# NEW_LINE_1.net
KiCad netlist of a schematic drawn in EAGLE
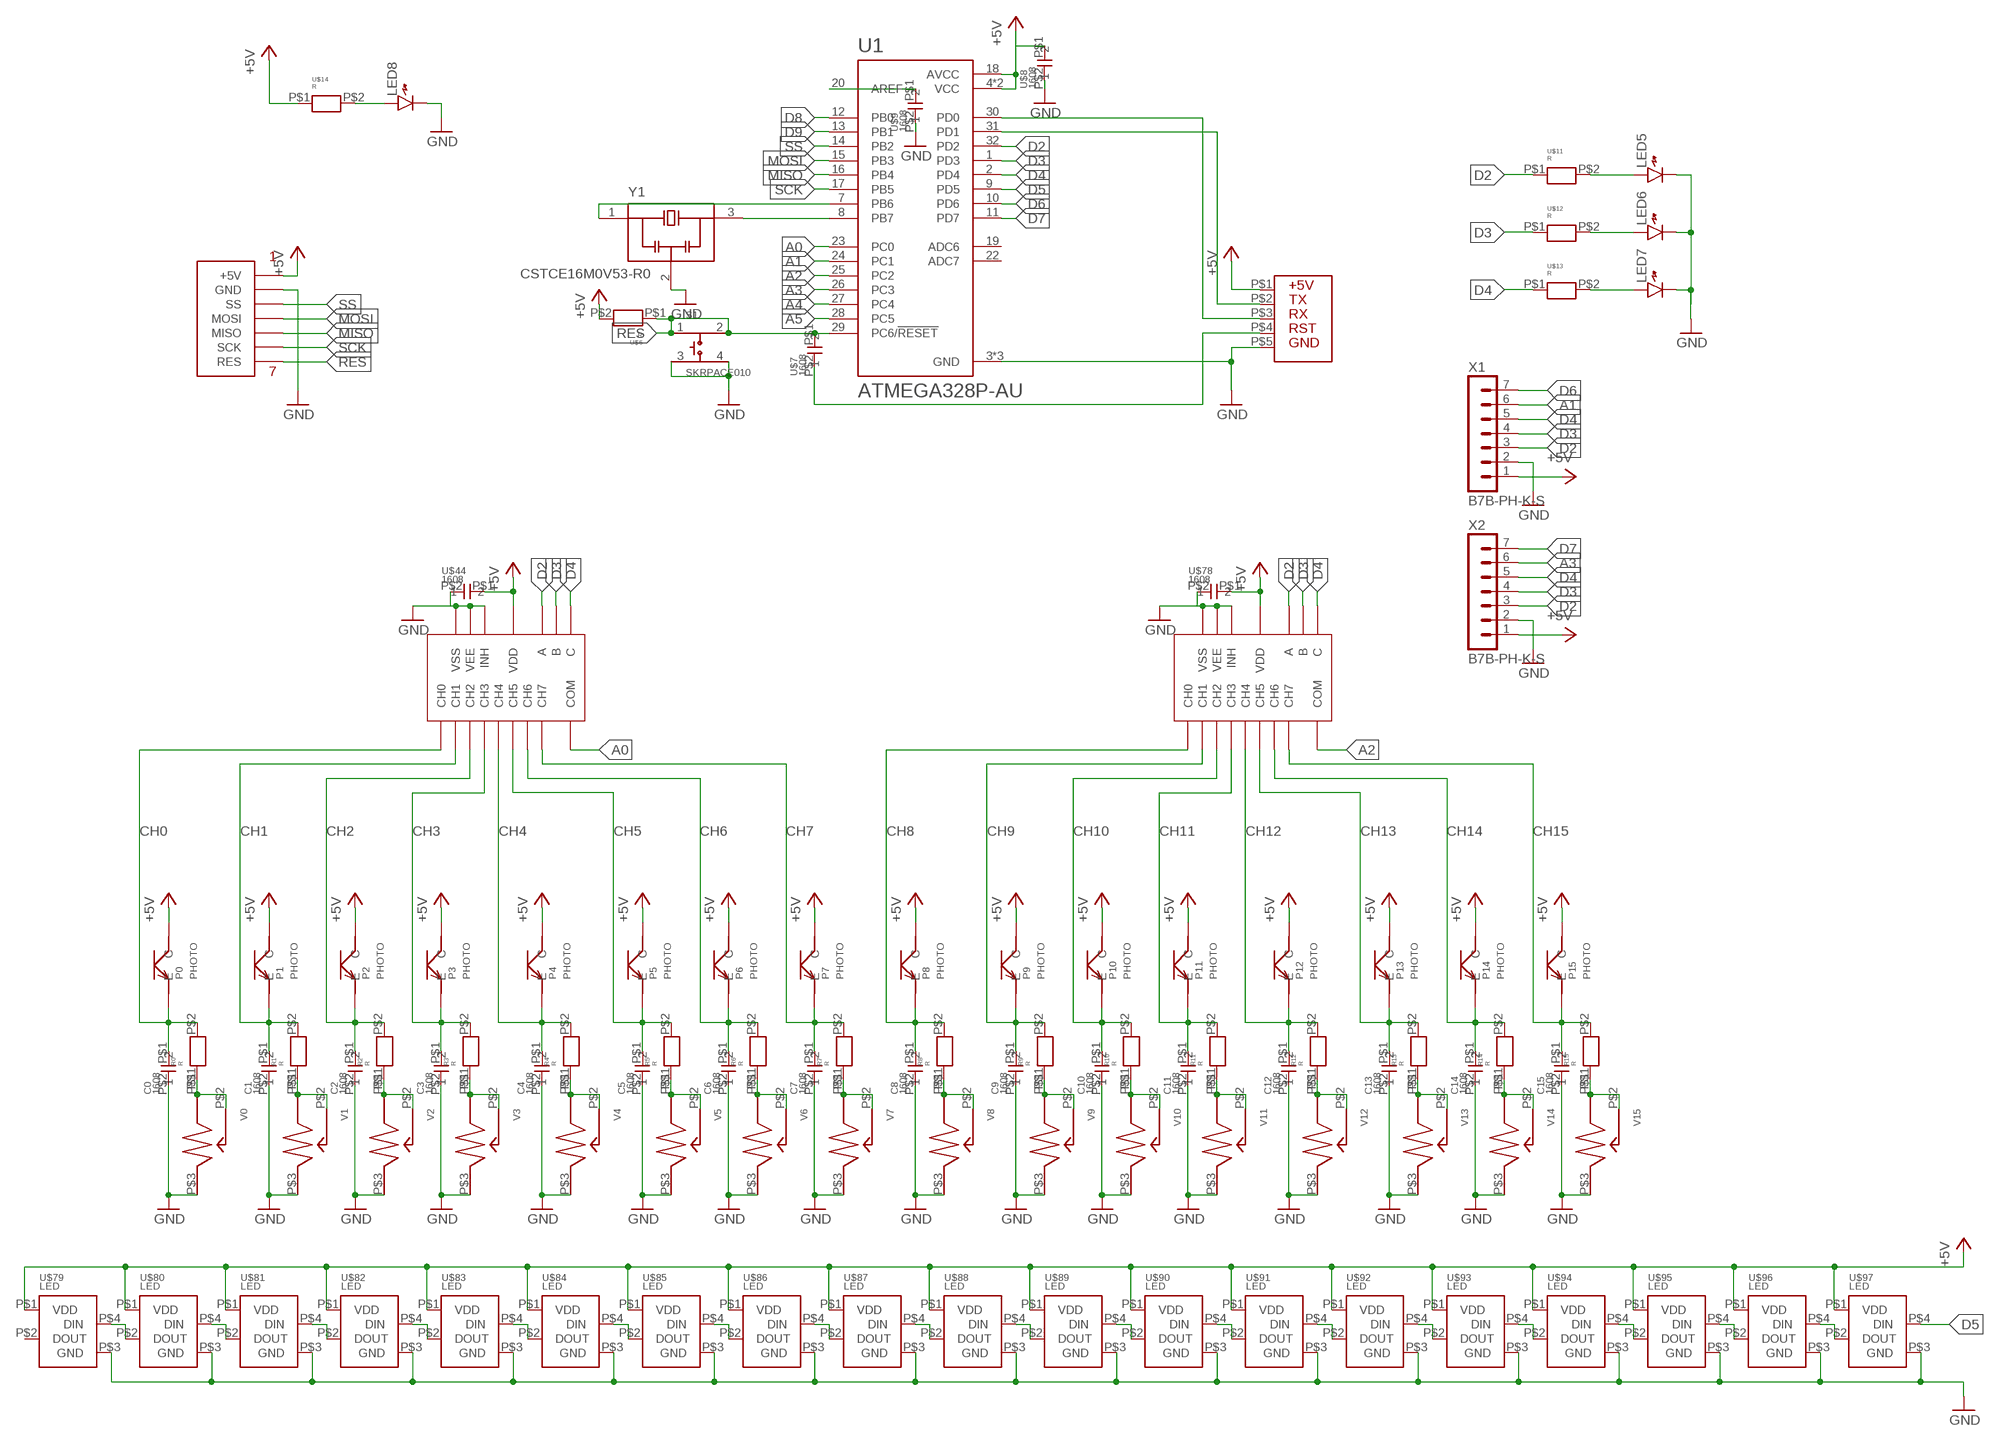
[diagram p0: schematic, sheet 1]

(export (version "E")
  (design (tool "Eeschema 10.0.6"))
  (components
    (comp (ref "C0")
      (value "1608")
      (footprint "eagle-import:CON")
      (libsource (lib "eagle-import") (part "1608"))
    )
    (comp (ref "C1")
      (value "1608")
      (footprint "eagle-import:CON")
      (libsource (lib "eagle-import") (part "1608"))
    )
    (comp (ref "C2")
      (value "1608")
      (footprint "eagle-import:CON")
      (libsource (lib "eagle-import") (part "1608"))
    )
    (comp (ref "C3")
      (value "1608")
      (footprint "eagle-import:CON")
      (libsource (lib "eagle-import") (part "1608"))
    )
    (comp (ref "C4")
      (value "1608")
      (footprint "eagle-import:CON")
      (libsource (lib "eagle-import") (part "1608"))
    )
    (comp (ref "C5")
      (value "1608")
      (footprint "eagle-import:CON")
      (libsource (lib "eagle-import") (part "1608"))
    )
    (comp (ref "C6")
      (value "1608")
      (footprint "eagle-import:CON")
      (libsource (lib "eagle-import") (part "1608"))
    )
    (comp (ref "C7")
      (value "1608")
      (footprint "eagle-import:CON")
      (libsource (lib "eagle-import") (part "1608"))
    )
    (comp (ref "C8")
      (value "1608")
      (footprint "eagle-import:CON")
      (libsource (lib "eagle-import") (part "1608"))
    )
    (comp (ref "C9")
      (value "1608")
      (footprint "eagle-import:CON")
      (libsource (lib "eagle-import") (part "1608"))
    )
    (comp (ref "C10")
      (value "1608")
      (footprint "eagle-import:CON")
      (libsource (lib "eagle-import") (part "1608"))
    )
    (comp (ref "C11")
      (value "1608")
      (footprint "eagle-import:CON")
      (libsource (lib "eagle-import") (part "1608"))
    )
    (comp (ref "C12")
      (value "1608")
      (footprint "eagle-import:CON")
      (libsource (lib "eagle-import") (part "1608"))
    )
    (comp (ref "C13")
      (value "1608")
      (footprint "eagle-import:CON")
      (libsource (lib "eagle-import") (part "1608"))
    )
    (comp (ref "C14")
      (value "1608")
      (footprint "eagle-import:CON")
      (libsource (lib "eagle-import") (part "1608"))
    )
    (comp (ref "C15")
      (value "1608")
      (footprint "eagle-import:CON")
      (libsource (lib "eagle-import") (part "1608"))
    )
    (comp (ref "LED5")
      (value "LED1608")
      (footprint "eagle-import:LED1608")
      (libsource (lib "eagle-import") (part "LED1608"))
    )
    (comp (ref "LED6")
      (value "LED1608")
      (footprint "eagle-import:LED1608")
      (libsource (lib "eagle-import") (part "LED1608"))
    )
    (comp (ref "LED7")
      (value "LED1608")
      (footprint "eagle-import:LED1608")
      (libsource (lib "eagle-import") (part "LED1608"))
    )
    (comp (ref "LED8")
      (value "LED1608")
      (footprint "eagle-import:LED1608")
      (libsource (lib "eagle-import") (part "LED1608"))
    )
    (comp (ref "P0")
      (value "PHOTO")
      (footprint "eagle-import:PHOTO")
      (libsource (lib "eagle-import") (part "PHOTO"))
    )
    (comp (ref "P1")
      (value "PHOTO")
      (footprint "eagle-import:PHOTO")
      (libsource (lib "eagle-import") (part "PHOTO"))
    )
    (comp (ref "P2")
      (value "PHOTO")
      (footprint "eagle-import:PHOTO")
      (libsource (lib "eagle-import") (part "PHOTO"))
    )
    (comp (ref "P3")
      (value "PHOTO")
      (footprint "eagle-import:PHOTO")
      (libsource (lib "eagle-import") (part "PHOTO"))
    )
    (comp (ref "P4")
      (value "PHOTO")
      (footprint "eagle-import:PHOTO")
      (libsource (lib "eagle-import") (part "PHOTO"))
    )
    (comp (ref "P5")
      (value "PHOTO")
      (footprint "eagle-import:PHOTO")
      (libsource (lib "eagle-import") (part "PHOTO"))
    )
    (comp (ref "P6")
      (value "PHOTO")
      (footprint "eagle-import:PHOTO")
      (libsource (lib "eagle-import") (part "PHOTO"))
    )
    (comp (ref "P7")
      (value "PHOTO")
      (footprint "eagle-import:PHOTO")
      (libsource (lib "eagle-import") (part "PHOTO"))
    )
    (comp (ref "P8")
      (value "PHOTO")
      (footprint "eagle-import:PHOTO")
      (libsource (lib "eagle-import") (part "PHOTO"))
    )
    (comp (ref "P9")
      (value "PHOTO")
      (footprint "eagle-import:PHOTO")
      (libsource (lib "eagle-import") (part "PHOTO"))
    )
    (comp (ref "P10")
      (value "PHOTO")
      (footprint "eagle-import:PHOTO")
      (libsource (lib "eagle-import") (part "PHOTO"))
    )
    (comp (ref "P11")
      (value "PHOTO")
      (footprint "eagle-import:PHOTO")
      (libsource (lib "eagle-import") (part "PHOTO"))
    )
    (comp (ref "P12")
      (value "PHOTO")
      (footprint "eagle-import:PHOTO")
      (libsource (lib "eagle-import") (part "PHOTO"))
    )
    (comp (ref "P13")
      (value "PHOTO")
      (footprint "eagle-import:PHOTO")
      (libsource (lib "eagle-import") (part "PHOTO"))
    )
    (comp (ref "P14")
      (value "PHOTO")
      (footprint "eagle-import:PHOTO")
      (libsource (lib "eagle-import") (part "PHOTO"))
    )
    (comp (ref "P15")
      (value "PHOTO")
      (footprint "eagle-import:PHOTO")
      (libsource (lib "eagle-import") (part "PHOTO"))
    )
    (comp (ref "R0") (value "R") (footprint "eagle-import:1608") (libsource (lib "eagle-import") (part "R")))
    (comp (ref "R1") (value "R") (footprint "eagle-import:1608") (libsource (lib "eagle-import") (part "R")))
    (comp (ref "R2") (value "R") (footprint "eagle-import:1608") (libsource (lib "eagle-import") (part "R")))
    (comp (ref "R3") (value "R") (footprint "eagle-import:1608") (libsource (lib "eagle-import") (part "R")))
    (comp (ref "R4") (value "R") (footprint "eagle-import:1608") (libsource (lib "eagle-import") (part "R")))
    (comp (ref "R5") (value "R") (footprint "eagle-import:1608") (libsource (lib "eagle-import") (part "R")))
    (comp (ref "R6") (value "R") (footprint "eagle-import:1608") (libsource (lib "eagle-import") (part "R")))
    (comp (ref "R7") (value "R") (footprint "eagle-import:1608") (libsource (lib "eagle-import") (part "R")))
    (comp (ref "R8") (value "R") (footprint "eagle-import:1608") (libsource (lib "eagle-import") (part "R")))
    (comp (ref "R9") (value "R") (footprint "eagle-import:1608") (libsource (lib "eagle-import") (part "R")))
    (comp (ref "R10") (value "R") (footprint "eagle-import:1608") (libsource (lib "eagle-import") (part "R")))
    (comp (ref "R11") (value "R") (footprint "eagle-import:1608") (libsource (lib "eagle-import") (part "R")))
    (comp (ref "R12") (value "R") (footprint "eagle-import:1608") (libsource (lib "eagle-import") (part "R")))
    (comp (ref "R13") (value "R") (footprint "eagle-import:1608") (libsource (lib "eagle-import") (part "R")))
    (comp (ref "R14") (value "R") (footprint "eagle-import:1608") (libsource (lib "eagle-import") (part "R")))
    (comp (ref "R15") (value "R") (footprint "eagle-import:1608") (libsource (lib "eagle-import") (part "R")))
    (comp (ref "S1")
      (value "SKRPACE010")
      (footprint "eagle-import:SW_SKRPACE010")
      (fields (field (name "MF") "ALPS"))
      (libsource (lib "eagle-import") (part "SKRPACE010"))
    )
    (comp (ref "U$1")
      (value "AM")
      (footprint "eagle-import:SOP65P640X120-16N")
      (libsource (lib "eagle-import") (part "AM"))
    )
    (comp (ref "U$6") (value "R") (footprint "eagle-import:1608") (libsource (lib "eagle-import") (part "R")))
    (comp (ref "U$7")
      (value "1608")
      (footprint "eagle-import:CON")
      (libsource (lib "eagle-import") (part "1608"))
    )
    (comp (ref "U$8")
      (value "1608")
      (footprint "eagle-import:CON")
      (libsource (lib "eagle-import") (part "1608"))
    )
    (comp (ref "U$9")
      (value "1608")
      (footprint "eagle-import:CON")
      (libsource (lib "eagle-import") (part "1608"))
    )
    (comp (ref "U$10")
      (value "SI")
      (footprint "eagle-import:SI")
      (libsource (lib "eagle-import") (part "SI"))
    )
    (comp (ref "U$11")
      (value "R")
      (footprint "eagle-import:1608")
      (libsource (lib "eagle-import") (part "R"))
    )
    (comp (ref "U$12")
      (value "R")
      (footprint "eagle-import:1608")
      (libsource (lib "eagle-import") (part "R"))
    )
    (comp (ref "U$13")
      (value "R")
      (footprint "eagle-import:1608")
      (libsource (lib "eagle-import") (part "R"))
    )
    (comp (ref "U$14")
      (value "R")
      (footprint "eagle-import:1608")
      (libsource (lib "eagle-import") (part "R"))
    )
    (comp (ref "U$15")
      (value "SPI")
      (footprint "eagle-import:SPI")
      (libsource (lib "eagle-import") (part "SPI"))
    )
    (comp (ref "U$44")
      (value "1608")
      (footprint "eagle-import:CON")
      (libsource (lib "eagle-import") (part "1608"))
    )
    (comp (ref "U$45")
      (value "AM")
      (footprint "eagle-import:SOP65P640X120-16N")
      (libsource (lib "eagle-import") (part "AM"))
    )
    (comp (ref "U$78")
      (value "1608")
      (footprint "eagle-import:CON")
      (libsource (lib "eagle-import") (part "1608"))
    )
    (comp (ref "U$79")
      (value "LED")
      (footprint "eagle-import:LED")
      (libsource (lib "eagle-import") (part "LED"))
    )
    (comp (ref "U$80")
      (value "LED")
      (footprint "eagle-import:LED")
      (libsource (lib "eagle-import") (part "LED"))
    )
    (comp (ref "U$81")
      (value "LED")
      (footprint "eagle-import:LED")
      (libsource (lib "eagle-import") (part "LED"))
    )
    (comp (ref "U$82")
      (value "LED")
      (footprint "eagle-import:LED")
      (libsource (lib "eagle-import") (part "LED"))
    )
    (comp (ref "U$83")
      (value "LED")
      (footprint "eagle-import:LED")
      (libsource (lib "eagle-import") (part "LED"))
    )
    (comp (ref "U$84")
      (value "LED")
      (footprint "eagle-import:LED")
      (libsource (lib "eagle-import") (part "LED"))
    )
    (comp (ref "U$85")
      (value "LED")
      (footprint "eagle-import:LED")
      (libsource (lib "eagle-import") (part "LED"))
    )
    (comp (ref "U$86")
      (value "LED")
      (footprint "eagle-import:LED")
      (libsource (lib "eagle-import") (part "LED"))
    )
    (comp (ref "U$87")
      (value "LED")
      (footprint "eagle-import:LED")
      (libsource (lib "eagle-import") (part "LED"))
    )
    (comp (ref "U$88")
      (value "LED")
      (footprint "eagle-import:LED")
      (libsource (lib "eagle-import") (part "LED"))
    )
    (comp (ref "U$89")
      (value "LED")
      (footprint "eagle-import:LED")
      (libsource (lib "eagle-import") (part "LED"))
    )
    (comp (ref "U$90")
      (value "LED")
      (footprint "eagle-import:LED")
      (libsource (lib "eagle-import") (part "LED"))
    )
    (comp (ref "U$91")
      (value "LED")
      (footprint "eagle-import:LED")
      (libsource (lib "eagle-import") (part "LED"))
    )
    (comp (ref "U$92")
      (value "LED")
      (footprint "eagle-import:LED")
      (libsource (lib "eagle-import") (part "LED"))
    )
    (comp (ref "U$93")
      (value "LED")
      (footprint "eagle-import:LED")
      (libsource (lib "eagle-import") (part "LED"))
    )
    (comp (ref "U$94")
      (value "LED")
      (footprint "eagle-import:LED")
      (libsource (lib "eagle-import") (part "LED"))
    )
    (comp (ref "U$95")
      (value "LED")
      (footprint "eagle-import:LED")
      (libsource (lib "eagle-import") (part "LED"))
    )
    (comp (ref "U$96")
      (value "LED")
      (footprint "eagle-import:LED")
      (libsource (lib "eagle-import") (part "LED"))
    )
    (comp (ref "U$97")
      (value "LED")
      (footprint "eagle-import:LED")
      (libsource (lib "eagle-import") (part "LED"))
    )
    (comp (ref "U1")
      (value "ATMEGA328P-AU")
      (footprint "eagle-import:QFP80P900X900X120-32N")
      (fields (field (name "MF") "Microchip Technology"))
      (libsource (lib "eagle-import") (part "ATMEGA328P-AU"))
    )
    (comp (ref "V0") (value "VR") (footprint "eagle-import:VR") (libsource (lib "eagle-import") (part "VR")))
    (comp (ref "V1") (value "VR") (footprint "eagle-import:VR") (libsource (lib "eagle-import") (part "VR")))
    (comp (ref "V2") (value "VR") (footprint "eagle-import:VR") (libsource (lib "eagle-import") (part "VR")))
    (comp (ref "V3") (value "VR") (footprint "eagle-import:VR") (libsource (lib "eagle-import") (part "VR")))
    (comp (ref "V4") (value "VR") (footprint "eagle-import:VR") (libsource (lib "eagle-import") (part "VR")))
    (comp (ref "V5") (value "VR") (footprint "eagle-import:VR") (libsource (lib "eagle-import") (part "VR")))
    (comp (ref "V6") (value "VR") (footprint "eagle-import:VR") (libsource (lib "eagle-import") (part "VR")))
    (comp (ref "V7") (value "VR") (footprint "eagle-import:VR") (libsource (lib "eagle-import") (part "VR")))
    (comp (ref "V8") (value "VR") (footprint "eagle-import:VR") (libsource (lib "eagle-import") (part "VR")))
    (comp (ref "V9") (value "VR") (footprint "eagle-import:VR") (libsource (lib "eagle-import") (part "VR")))
    (comp (ref "V10") (value "VR") (footprint "eagle-import:VR") (libsource (lib "eagle-import") (part "VR")))
    (comp (ref "V11") (value "VR") (footprint "eagle-import:VR") (libsource (lib "eagle-import") (part "VR")))
    (comp (ref "V12") (value "VR") (footprint "eagle-import:VR") (libsource (lib "eagle-import") (part "VR")))
    (comp (ref "V13") (value "VR") (footprint "eagle-import:VR") (libsource (lib "eagle-import") (part "VR")))
    (comp (ref "V14") (value "VR") (footprint "eagle-import:VR") (libsource (lib "eagle-import") (part "VR")))
    (comp (ref "V15") (value "VR") (footprint "eagle-import:VR") (libsource (lib "eagle-import") (part "VR")))
    (comp (ref "X1")
      (value "B7B-PH-K-S")
      (footprint "eagle-import:B7B-PH-K-S")
      (libsource (lib "eagle-import") (part "B7B-PH-K-S"))
    )
    (comp (ref "X2")
      (value "B7B-PH-K-S")
      (footprint "eagle-import:B7B-PH-K-S")
      (libsource (lib "eagle-import") (part "B7B-PH-K-S"))
    )
    (comp (ref "Y1")
      (value "CSTCE16M0V53-R0")
      (footprint "eagle-import:OSC_CSTCE16M0V53-R0")
      (fields (field (name "MANUFACTURER") "Murata"))
      (libsource (lib "eagle-import") (part "CSTCE16M0V53-R0"))
    )
  )
  (nets
    (net (code "1") (name "+5V") (class "Default")
      (node (ref "P0") (pin "P$1") (pinfunction "C_P$1") (pintype "bidirectional"))
      (node (ref "P1") (pin "P$1") (pinfunction "C_P$1") (pintype "bidirectional"))
      (node (ref "P10") (pin "P$1") (pinfunction "C_P$1") (pintype "bidirectional"))
      (node (ref "P11") (pin "P$1") (pinfunction "C_P$1") (pintype "bidirectional"))
      (node (ref "P12") (pin "P$1") (pinfunction "C_P$1") (pintype "bidirectional"))
      (node (ref "P13") (pin "P$1") (pinfunction "C_P$1") (pintype "bidirectional"))
      (node (ref "P14") (pin "P$1") (pinfunction "C_P$1") (pintype "bidirectional"))
      (node (ref "P15") (pin "P$1") (pinfunction "C_P$1") (pintype "bidirectional"))
      (node (ref "P2") (pin "P$1") (pinfunction "C_P$1") (pintype "bidirectional"))
      (node (ref "P3") (pin "P$1") (pinfunction "C_P$1") (pintype "bidirectional"))
      (node (ref "P4") (pin "P$1") (pinfunction "C_P$1") (pintype "bidirectional"))
      (node (ref "P5") (pin "P$1") (pinfunction "C_P$1") (pintype "bidirectional"))
      (node (ref "P6") (pin "P$1") (pinfunction "C_P$1") (pintype "bidirectional"))
      (node (ref "P7") (pin "P$1") (pinfunction "C_P$1") (pintype "bidirectional"))
      (node (ref "P8") (pin "P$1") (pinfunction "C_P$1") (pintype "bidirectional"))
      (node (ref "P9") (pin "P$1") (pinfunction "C_P$1") (pintype "bidirectional"))
      (node (ref "U$1") (pin "16") (pinfunction "VDD_16") (pintype "bidirectional"))
      (node (ref "U$10") (pin "P$1") (pinfunction "P$1_P$1") (pintype "bidirectional"))
      (node (ref "U$14") (pin "P$1") (pinfunction "P$1_P$1") (pintype "bidirectional"))
      (node (ref "U$15") (pin "P$1") (pinfunction "+5V_P$1") (pintype "bidirectional"))
      (node (ref "U$44") (pin "P$1") (pinfunction "1_P$1") (pintype "bidirectional"))
      (node (ref "U$45") (pin "16") (pinfunction "VDD_16") (pintype "bidirectional"))
      (node (ref "U$6") (pin "P$2") (pinfunction "P$2_P$2") (pintype "bidirectional"))
      (node (ref "U$78") (pin "P$1") (pinfunction "1_P$1") (pintype "bidirectional"))
      (node (ref "U$79") (pin "P$1") (pinfunction "VDD_P$1") (pintype "bidirectional"))
      (node (ref "U$8") (pin "P$1") (pinfunction "1_P$1") (pintype "bidirectional"))
      (node (ref "U$80") (pin "P$1") (pinfunction "VDD_P$1") (pintype "bidirectional"))
      (node (ref "U$81") (pin "P$1") (pinfunction "VDD_P$1") (pintype "bidirectional"))
      (node (ref "U$82") (pin "P$1") (pinfunction "VDD_P$1") (pintype "bidirectional"))
      (node (ref "U$83") (pin "P$1") (pinfunction "VDD_P$1") (pintype "bidirectional"))
      (node (ref "U$84") (pin "P$1") (pinfunction "VDD_P$1") (pintype "bidirectional"))
      (node (ref "U$85") (pin "P$1") (pinfunction "VDD_P$1") (pintype "bidirectional"))
      (node (ref "U$86") (pin "P$1") (pinfunction "VDD_P$1") (pintype "bidirectional"))
      (node (ref "U$87") (pin "P$1") (pinfunction "VDD_P$1") (pintype "bidirectional"))
      (node (ref "U$88") (pin "P$1") (pinfunction "VDD_P$1") (pintype "bidirectional"))
      (node (ref "U$89") (pin "P$1") (pinfunction "VDD_P$1") (pintype "bidirectional"))
      (node (ref "U$90") (pin "P$1") (pinfunction "VDD_P$1") (pintype "bidirectional"))
      (node (ref "U$91") (pin "P$1") (pinfunction "VDD_P$1") (pintype "bidirectional"))
      (node (ref "U$92") (pin "P$1") (pinfunction "VDD_P$1") (pintype "bidirectional"))
      (node (ref "U$93") (pin "P$1") (pinfunction "VDD_P$1") (pintype "bidirectional"))
      (node (ref "U$94") (pin "P$1") (pinfunction "VDD_P$1") (pintype "bidirectional"))
      (node (ref "U$95") (pin "P$1") (pinfunction "VDD_P$1") (pintype "bidirectional"))
      (node (ref "U$96") (pin "P$1") (pinfunction "VDD_P$1") (pintype "bidirectional"))
      (node (ref "U$97") (pin "P$1") (pinfunction "VDD_P$1") (pintype "bidirectional"))
      (node (ref "U1") (pin "18") (pinfunction "AVCC_18") (pintype "power_in"))
      (node (ref "U1") (pin "4") (pinfunction "VCC_4") (pintype "power_in"))
      (node (ref "U1") (pin "6") (pinfunction "VCC_6") (pintype "power_in"))
      (node (ref "X1") (pin "1") (pinfunction "1_1") (pintype "passive"))
      (node (ref "X2") (pin "1") (pinfunction "1_1") (pintype "passive"))
    )
    (net (code "2") (name "A0") (class "Default")
      (node (ref "U$1") (pin "3") (pinfunction "COM_3") (pintype "bidirectional"))
      (node (ref "U1") (pin "23") (pinfunction "PC0_23") (pintype "bidirectional"))
    )
    (net (code "3") (name "A1") (class "Default")
      (node (ref "U1") (pin "24") (pinfunction "PC1_24") (pintype "bidirectional"))
      (node (ref "X1") (pin "6") (pinfunction "6_6") (pintype "passive"))
    )
    (net (code "4") (name "A2") (class "Default")
      (node (ref "U$45") (pin "3") (pinfunction "COM_3") (pintype "bidirectional"))
      (node (ref "U1") (pin "25") (pinfunction "PC2_25") (pintype "bidirectional"))
    )
    (net (code "5") (name "A3") (class "Default")
      (node (ref "U1") (pin "26") (pinfunction "PC3_26") (pintype "bidirectional"))
      (node (ref "X2") (pin "6") (pinfunction "6_6") (pintype "passive"))
    )
    (net (code "6") (name "A4") (class "Default")
      (node (ref "U1") (pin "27") (pinfunction "PC4_27") (pintype "bidirectional"))
    )
    (net (code "7") (name "A5") (class "Default")
      (node (ref "U1") (pin "28") (pinfunction "PC5_28") (pintype "bidirectional"))
    )
    (net (code "8") (name "CH0") (class "Default")
      (node (ref "C0") (pin "P$1") (pinfunction "1_P$1") (pintype "bidirectional"))
      (node (ref "P0") (pin "P$2") (pinfunction "E_P$2") (pintype "bidirectional"))
      (node (ref "R0") (pin "P$2") (pinfunction "P$2_P$2") (pintype "bidirectional"))
      (node (ref "U$1") (pin "13") (pinfunction "CH0_13") (pintype "bidirectional"))
    )
    (net (code "9") (name "CH1") (class "Default")
      (node (ref "C1") (pin "P$1") (pinfunction "1_P$1") (pintype "bidirectional"))
      (node (ref "P1") (pin "P$2") (pinfunction "E_P$2") (pintype "bidirectional"))
      (node (ref "R1") (pin "P$2") (pinfunction "P$2_P$2") (pintype "bidirectional"))
      (node (ref "U$1") (pin "14") (pinfunction "CH1_14") (pintype "bidirectional"))
    )
    (net (code "10") (name "CH2") (class "Default")
      (node (ref "C2") (pin "P$1") (pinfunction "1_P$1") (pintype "bidirectional"))
      (node (ref "P2") (pin "P$2") (pinfunction "E_P$2") (pintype "bidirectional"))
      (node (ref "R2") (pin "P$2") (pinfunction "P$2_P$2") (pintype "bidirectional"))
      (node (ref "U$1") (pin "15") (pinfunction "CH2_15") (pintype "bidirectional"))
    )
    (net (code "11") (name "CH3") (class "Default")
      (node (ref "C3") (pin "P$1") (pinfunction "1_P$1") (pintype "bidirectional"))
      (node (ref "P3") (pin "P$2") (pinfunction "E_P$2") (pintype "bidirectional"))
      (node (ref "R3") (pin "P$2") (pinfunction "P$2_P$2") (pintype "bidirectional"))
      (node (ref "U$1") (pin "12") (pinfunction "CH3_12") (pintype "bidirectional"))
    )
    (net (code "12") (name "CH4") (class "Default")
      (node (ref "C4") (pin "P$1") (pinfunction "1_P$1") (pintype "bidirectional"))
      (node (ref "P4") (pin "P$2") (pinfunction "E_P$2") (pintype "bidirectional"))
      (node (ref "R4") (pin "P$2") (pinfunction "P$2_P$2") (pintype "bidirectional"))
      (node (ref "U$1") (pin "1") (pinfunction "CH4_1") (pintype "bidirectional"))
    )
    (net (code "13") (name "CH5") (class "Default")
      (node (ref "C5") (pin "P$1") (pinfunction "1_P$1") (pintype "bidirectional"))
      (node (ref "P5") (pin "P$2") (pinfunction "E_P$2") (pintype "bidirectional"))
      (node (ref "R5") (pin "P$2") (pinfunction "P$2_P$2") (pintype "bidirectional"))
      (node (ref "U$1") (pin "5") (pinfunction "CH5_5") (pintype "bidirectional"))
    )
    (net (code "14") (name "CH6") (class "Default")
      (node (ref "C6") (pin "P$1") (pinfunction "1_P$1") (pintype "bidirectional"))
      (node (ref "P6") (pin "P$2") (pinfunction "E_P$2") (pintype "bidirectional"))
      (node (ref "R6") (pin "P$2") (pinfunction "P$2_P$2") (pintype "bidirectional"))
      (node (ref "U$1") (pin "2") (pinfunction "CH6_2") (pintype "bidirectional"))
    )
    (net (code "15") (name "CH7") (class "Default")
      (node (ref "C7") (pin "P$1") (pinfunction "1_P$1") (pintype "bidirectional"))
      (node (ref "P7") (pin "P$2") (pinfunction "E_P$2") (pintype "bidirectional"))
      (node (ref "R7") (pin "P$2") (pinfunction "P$2_P$2") (pintype "bidirectional"))
      (node (ref "U$1") (pin "4") (pinfunction "CH7_4") (pintype "bidirectional"))
    )
    (net (code "16") (name "CH8") (class "Default")
      (node (ref "C8") (pin "P$1") (pinfunction "1_P$1") (pintype "bidirectional"))
      (node (ref "P8") (pin "P$2") (pinfunction "E_P$2") (pintype "bidirectional"))
      (node (ref "R8") (pin "P$2") (pinfunction "P$2_P$2") (pintype "bidirectional"))
      (node (ref "U$45") (pin "13") (pinfunction "CH0_13") (pintype "bidirectional"))
    )
    (net (code "17") (name "CH9") (class "Default")
      (node (ref "C9") (pin "P$1") (pinfunction "1_P$1") (pintype "bidirectional"))
      (node (ref "P9") (pin "P$2") (pinfunction "E_P$2") (pintype "bidirectional"))
      (node (ref "R9") (pin "P$2") (pinfunction "P$2_P$2") (pintype "bidirectional"))
      (node (ref "U$45") (pin "14") (pinfunction "CH1_14") (pintype "bidirectional"))
    )
    (net (code "18") (name "CH10") (class "Default")
      (node (ref "C10") (pin "P$1") (pinfunction "1_P$1") (pintype "bidirectional"))
      (node (ref "P10") (pin "P$2") (pinfunction "E_P$2") (pintype "bidirectional"))
      (node (ref "R10") (pin "P$2") (pinfunction "P$2_P$2") (pintype "bidirectional"))
      (node (ref "U$45") (pin "15") (pinfunction "CH2_15") (pintype "bidirectional"))
    )
    (net (code "19") (name "CH11") (class "Default")
      (node (ref "C11") (pin "P$1") (pinfunction "1_P$1") (pintype "bidirectional"))
      (node (ref "P11") (pin "P$2") (pinfunction "E_P$2") (pintype "bidirectional"))
      (node (ref "R11") (pin "P$2") (pinfunction "P$2_P$2") (pintype "bidirectional"))
      (node (ref "U$45") (pin "12") (pinfunction "CH3_12") (pintype "bidirectional"))
    )
    (net (code "20") (name "CH12") (class "Default")
      (node (ref "C12") (pin "P$1") (pinfunction "1_P$1") (pintype "bidirectional"))
      (node (ref "P12") (pin "P$2") (pinfunction "E_P$2") (pintype "bidirectional"))
      (node (ref "R12") (pin "P$2") (pinfunction "P$2_P$2") (pintype "bidirectional"))
      (node (ref "U$45") (pin "1") (pinfunction "CH4_1") (pintype "bidirectional"))
    )
    (net (code "21") (name "CH13") (class "Default")
      (node (ref "C13") (pin "P$1") (pinfunction "1_P$1") (pintype "bidirectional"))
      (node (ref "P13") (pin "P$2") (pinfunction "E_P$2") (pintype "bidirectional"))
      (node (ref "R13") (pin "P$2") (pinfunction "P$2_P$2") (pintype "bidirectional"))
      (node (ref "U$45") (pin "5") (pinfunction "CH5_5") (pintype "bidirectional"))
    )
    (net (code "22") (name "CH14") (class "Default")
      (node (ref "C14") (pin "P$1") (pinfunction "1_P$1") (pintype "bidirectional"))
      (node (ref "P14") (pin "P$2") (pinfunction "E_P$2") (pintype "bidirectional"))
      (node (ref "R14") (pin "P$2") (pinfunction "P$2_P$2") (pintype "bidirectional"))
      (node (ref "U$45") (pin "2") (pinfunction "CH6_2") (pintype "bidirectional"))
    )
    (net (code "23") (name "CH15") (class "Default")
      (node (ref "C15") (pin "P$1") (pinfunction "1_P$1") (pintype "bidirectional"))
      (node (ref "P15") (pin "P$2") (pinfunction "E_P$2") (pintype "bidirectional"))
      (node (ref "R15") (pin "P$2") (pinfunction "P$2_P$2") (pintype "bidirectional"))
      (node (ref "U$45") (pin "4") (pinfunction "CH7_4") (pintype "bidirectional"))
    )
    (net (code "24") (name "D2") (class "Default")
      (node (ref "U$1") (pin "11") (pinfunction "A_11") (pintype "bidirectional"))
      (node (ref "U$11") (pin "P$1") (pinfunction "P$1_P$1") (pintype "bidirectional"))
      (node (ref "U$45") (pin "11") (pinfunction "A_11") (pintype "bidirectional"))
      (node (ref "U1") (pin "32") (pinfunction "PD2_32") (pintype "bidirectional"))
      (node (ref "X1") (pin "3") (pinfunction "3_3") (pintype "passive"))
      (node (ref "X2") (pin "3") (pinfunction "3_3") (pintype "passive"))
    )
    (net (code "25") (name "D3") (class "Default")
      (node (ref "U$1") (pin "10") (pinfunction "B_10") (pintype "bidirectional"))
      (node (ref "U$12") (pin "P$1") (pinfunction "P$1_P$1") (pintype "bidirectional"))
      (node (ref "U$45") (pin "10") (pinfunction "B_10") (pintype "bidirectional"))
      (node (ref "U1") (pin "1") (pinfunction "PD3_1") (pintype "bidirectional"))
      (node (ref "X1") (pin "4") (pinfunction "4_4") (pintype "passive"))
      (node (ref "X2") (pin "4") (pinfunction "4_4") (pintype "passive"))
    )
    (net (code "26") (name "D4") (class "Default")
      (node (ref "U$1") (pin "9") (pinfunction "C_9") (pintype "bidirectional"))
      (node (ref "U$13") (pin "P$1") (pinfunction "P$1_P$1") (pintype "bidirectional"))
      (node (ref "U$45") (pin "9") (pinfunction "C_9") (pintype "bidirectional"))
      (node (ref "U1") (pin "2") (pinfunction "PD4_2") (pintype "bidirectional"))
      (node (ref "X1") (pin "5") (pinfunction "5_5") (pintype "passive"))
      (node (ref "X2") (pin "5") (pinfunction "5_5") (pintype "passive"))
    )
    (net (code "27") (name "D5") (class "Default")
      (node (ref "U$97") (pin "P$4") (pinfunction "DIN_P$4") (pintype "bidirectional"))
      (node (ref "U1") (pin "9") (pinfunction "PD5_9") (pintype "bidirectional"))
    )
    (net (code "28") (name "D6") (class "Default")
      (node (ref "U1") (pin "10") (pinfunction "PD6_10") (pintype "bidirectional"))
      (node (ref "X1") (pin "7") (pinfunction "7_7") (pintype "passive"))
    )
    (net (code "29") (name "D7") (class "Default")
      (node (ref "U1") (pin "11") (pinfunction "PD7_11") (pintype "bidirectional"))
      (node (ref "X2") (pin "7") (pinfunction "7_7") (pintype "passive"))
    )
    (net (code "30") (name "D8") (class "Default")
      (node (ref "U1") (pin "12") (pinfunction "PB0_12") (pintype "bidirectional"))
    )
    (net (code "31") (name "D9") (class "Default")
      (node (ref "U1") (pin "13") (pinfunction "PB1_13") (pintype "bidirectional"))
    )
    (net (code "32") (name "GND") (class "Default")
      (node (ref "C0") (pin "P$2") (pinfunction "2_P$2") (pintype "bidirectional"))
      (node (ref "C1") (pin "P$2") (pinfunction "2_P$2") (pintype "bidirectional"))
      (node (ref "C10") (pin "P$2") (pinfunction "2_P$2") (pintype "bidirectional"))
      (node (ref "C11") (pin "P$2") (pinfunction "2_P$2") (pintype "bidirectional"))
      (node (ref "C12") (pin "P$2") (pinfunction "2_P$2") (pintype "bidirectional"))
      (node (ref "C13") (pin "P$2") (pinfunction "2_P$2") (pintype "bidirectional"))
      (node (ref "C14") (pin "P$2") (pinfunction "2_P$2") (pintype "bidirectional"))
      (node (ref "C15") (pin "P$2") (pinfunction "2_P$2") (pintype "bidirectional"))
      (node (ref "C2") (pin "P$2") (pinfunction "2_P$2") (pintype "bidirectional"))
      (node (ref "C3") (pin "P$2") (pinfunction "2_P$2") (pintype "bidirectional"))
      (node (ref "C4") (pin "P$2") (pinfunction "2_P$2") (pintype "bidirectional"))
      (node (ref "C5") (pin "P$2") (pinfunction "2_P$2") (pintype "bidirectional"))
      (node (ref "C6") (pin "P$2") (pinfunction "2_P$2") (pintype "bidirectional"))
      (node (ref "C7") (pin "P$2") (pinfunction "2_P$2") (pintype "bidirectional"))
      (node (ref "C8") (pin "P$2") (pinfunction "2_P$2") (pintype "bidirectional"))
      (node (ref "C9") (pin "P$2") (pinfunction "2_P$2") (pintype "bidirectional"))
      (node (ref "LED5") (pin "K") (pinfunction "K_K") (pintype "passive"))
      (node (ref "LED6") (pin "K") (pinfunction "K_K") (pintype "passive"))
      (node (ref "LED7") (pin "K") (pinfunction "K_K") (pintype "passive"))
      (node (ref "LED8") (pin "K") (pinfunction "K_K") (pintype "passive"))
      (node (ref "S1") (pin "3") (pinfunction "3_3") (pintype "bidirectional"))
      (node (ref "S1") (pin "4") (pinfunction "4_4") (pintype "bidirectional"))
      (node (ref "U$1") (pin "6") (pinfunction "INH_6") (pintype "bidirectional"))
      (node (ref "U$1") (pin "7") (pinfunction "VEE_7") (pintype "bidirectional"))
      (node (ref "U$1") (pin "8") (pinfunction "VSS_8") (pintype "bidirectional"))
      (node (ref "U$10") (pin "P$5") (pinfunction "P$5_P$5") (pintype "bidirectional"))
      (node (ref "U$15") (pin "P$2") (pinfunction "GND_P$2") (pintype "bidirectional"))
      (node (ref "U$44") (pin "P$2") (pinfunction "2_P$2") (pintype "bidirectional"))
      (node (ref "U$45") (pin "6") (pinfunction "INH_6") (pintype "bidirectional"))
      (node (ref "U$45") (pin "7") (pinfunction "VEE_7") (pintype "bidirectional"))
      (node (ref "U$45") (pin "8") (pinfunction "VSS_8") (pintype "bidirectional"))
      (node (ref "U$78") (pin "P$2") (pinfunction "2_P$2") (pintype "bidirectional"))
      (node (ref "U$79") (pin "P$3") (pinfunction "GND_P$3") (pintype "bidirectional"))
      (node (ref "U$8") (pin "P$2") (pinfunction "2_P$2") (pintype "bidirectional"))
      (node (ref "U$80") (pin "P$3") (pinfunction "GND_P$3") (pintype "bidirectional"))
      (node (ref "U$81") (pin "P$3") (pinfunction "GND_P$3") (pintype "bidirectional"))
      (node (ref "U$82") (pin "P$3") (pinfunction "GND_P$3") (pintype "bidirectional"))
      (node (ref "U$83") (pin "P$3") (pinfunction "GND_P$3") (pintype "bidirectional"))
      (node (ref "U$84") (pin "P$3") (pinfunction "GND_P$3") (pintype "bidirectional"))
      (node (ref "U$85") (pin "P$3") (pinfunction "GND_P$3") (pintype "bidirectional"))
      (node (ref "U$86") (pin "P$3") (pinfunction "GND_P$3") (pintype "bidirectional"))
      (node (ref "U$87") (pin "P$3") (pinfunction "GND_P$3") (pintype "bidirectional"))
      (node (ref "U$88") (pin "P$3") (pinfunction "GND_P$3") (pintype "bidirectional"))
      (node (ref "U$89") (pin "P$3") (pinfunction "GND_P$3") (pintype "bidirectional"))
      (node (ref "U$9") (pin "P$2") (pinfunction "2_P$2") (pintype "bidirectional"))
      (node (ref "U$90") (pin "P$3") (pinfunction "GND_P$3") (pintype "bidirectional"))
      (node (ref "U$91") (pin "P$3") (pinfunction "GND_P$3") (pintype "bidirectional"))
      (node (ref "U$92") (pin "P$3") (pinfunction "GND_P$3") (pintype "bidirectional"))
      (node (ref "U$93") (pin "P$3") (pinfunction "GND_P$3") (pintype "bidirectional"))
      (node (ref "U$94") (pin "P$3") (pinfunction "GND_P$3") (pintype "bidirectional"))
      (node (ref "U$95") (pin "P$3") (pinfunction "GND_P$3") (pintype "bidirectional"))
      (node (ref "U$96") (pin "P$3") (pinfunction "GND_P$3") (pintype "bidirectional"))
      (node (ref "U$97") (pin "P$3") (pinfunction "GND_P$3") (pintype "bidirectional"))
      (node (ref "U1") (pin "21") (pinfunction "GND_21") (pintype "power_in"))
      (node (ref "U1") (pin "3") (pinfunction "GND_3") (pintype "power_in"))
      (node (ref "U1") (pin "5") (pinfunction "GND_5") (pintype "power_in"))
      (node (ref "V0") (pin "P$3") (pinfunction "P$3_P$3") (pintype "bidirectional"))
      (node (ref "V1") (pin "P$3") (pinfunction "P$3_P$3") (pintype "bidirectional"))
      (node (ref "V10") (pin "P$3") (pinfunction "P$3_P$3") (pintype "bidirectional"))
      (node (ref "V11") (pin "P$3") (pinfunction "P$3_P$3") (pintype "bidirectional"))
      (node (ref "V12") (pin "P$3") (pinfunction "P$3_P$3") (pintype "bidirectional"))
      (node (ref "V13") (pin "P$3") (pinfunction "P$3_P$3") (pintype "bidirectional"))
      (node (ref "V14") (pin "P$3") (pinfunction "P$3_P$3") (pintype "bidirectional"))
      (node (ref "V15") (pin "P$3") (pinfunction "P$3_P$3") (pintype "bidirectional"))
      (node (ref "V2") (pin "P$3") (pinfunction "P$3_P$3") (pintype "bidirectional"))
      (node (ref "V3") (pin "P$3") (pinfunction "P$3_P$3") (pintype "bidirectional"))
      (node (ref "V4") (pin "P$3") (pinfunction "P$3_P$3") (pintype "bidirectional"))
      (node (ref "V5") (pin "P$3") (pinfunction "P$3_P$3") (pintype "bidirectional"))
      (node (ref "V6") (pin "P$3") (pinfunction "P$3_P$3") (pintype "bidirectional"))
      (node (ref "V7") (pin "P$3") (pinfunction "P$3_P$3") (pintype "bidirectional"))
      (node (ref "V8") (pin "P$3") (pinfunction "P$3_P$3") (pintype "bidirectional"))
      (node (ref "V9") (pin "P$3") (pinfunction "P$3_P$3") (pintype "bidirectional"))
      (node (ref "X1") (pin "2") (pinfunction "2_2") (pintype "passive"))
      (node (ref "X2") (pin "2") (pinfunction "2_2") (pintype "passive"))
      (node (ref "Y1") (pin "2") (pinfunction "GND_2") (pintype "power_in"))
    )
    (net (code "33") (name "MISO") (class "Default")
      (node (ref "U$15") (pin "P$5") (pinfunction "MISO_P$5") (pintype "bidirectional"))
      (node (ref "U1") (pin "16") (pinfunction "PB4_16") (pintype "bidirectional"))
    )
    (net (code "34") (name "MOSI") (class "Default")
      (node (ref "U$15") (pin "P$4") (pinfunction "MOSI_P$4") (pintype "bidirectional"))
      (node (ref "U1") (pin "15") (pinfunction "PB3_15") (pintype "bidirectional"))
    )
    (net (code "35") (name "Net-(LED5-PadA)") (class "Default")
      (node (ref "LED5") (pin "A") (pinfunction "A_A") (pintype "passive"))
      (node (ref "U$11") (pin "P$2") (pinfunction "P$2_P$2") (pintype "bidirectional"))
    )
    (net (code "36") (name "Net-(LED6-PadA)") (class "Default")
      (node (ref "LED6") (pin "A") (pinfunction "A_A") (pintype "passive"))
      (node (ref "U$12") (pin "P$2") (pinfunction "P$2_P$2") (pintype "bidirectional"))
    )
    (net (code "37") (name "Net-(LED7-PadA)") (class "Default")
      (node (ref "LED7") (pin "A") (pinfunction "A_A") (pintype "passive"))
      (node (ref "U$13") (pin "P$2") (pinfunction "P$2_P$2") (pintype "bidirectional"))
    )
    (net (code "38") (name "Net-(LED8-PadA)") (class "Default")
      (node (ref "LED8") (pin "A") (pinfunction "A_A") (pintype "passive"))
      (node (ref "U$14") (pin "P$2") (pinfunction "P$2_P$2") (pintype "bidirectional"))
    )
    (net (code "39") (name "Net-(R0-PadP$1)") (class "Default")
      (node (ref "R0") (pin "P$1") (pinfunction "P$1_P$1") (pintype "bidirectional"))
      (node (ref "V0") (pin "P$1") (pinfunction "P$1_P$1") (pintype "bidirectional"))
      (node (ref "V0") (pin "P$2") (pinfunction "P$2_P$2") (pintype "bidirectional"))
    )
    (net (code "40") (name "Net-(R1-PadP$1)") (class "Default")
      (node (ref "R1") (pin "P$1") (pinfunction "P$1_P$1") (pintype "bidirectional"))
      (node (ref "V1") (pin "P$1") (pinfunction "P$1_P$1") (pintype "bidirectional"))
      (node (ref "V1") (pin "P$2") (pinfunction "P$2_P$2") (pintype "bidirectional"))
    )
    (net (code "41") (name "Net-(R2-PadP$1)") (class "Default")
      (node (ref "R2") (pin "P$1") (pinfunction "P$1_P$1") (pintype "bidirectional"))
      (node (ref "V2") (pin "P$1") (pinfunction "P$1_P$1") (pintype "bidirectional"))
      (node (ref "V2") (pin "P$2") (pinfunction "P$2_P$2") (pintype "bidirectional"))
    )
    (net (code "42") (name "Net-(R3-PadP$1)") (class "Default")
      (node (ref "R3") (pin "P$1") (pinfunction "P$1_P$1") (pintype "bidirectional"))
      (node (ref "V3") (pin "P$1") (pinfunction "P$1_P$1") (pintype "bidirectional"))
      (node (ref "V3") (pin "P$2") (pinfunction "P$2_P$2") (pintype "bidirectional"))
    )
    (net (code "43") (name "Net-(R4-PadP$1)") (class "Default")
      (node (ref "R4") (pin "P$1") (pinfunction "P$1_P$1") (pintype "bidirectional"))
      (node (ref "V4") (pin "P$1") (pinfunction "P$1_P$1") (pintype "bidirectional"))
      (node (ref "V4") (pin "P$2") (pinfunction "P$2_P$2") (pintype "bidirectional"))
    )
    (net (code "44") (name "Net-(R5-PadP$1)") (class "Default")
      (node (ref "R5") (pin "P$1") (pinfunction "P$1_P$1") (pintype "bidirectional"))
      (node (ref "V5") (pin "P$1") (pinfunction "P$1_P$1") (pintype "bidirectional"))
      (node (ref "V5") (pin "P$2") (pinfunction "P$2_P$2") (pintype "bidirectional"))
    )
    (net (code "45") (name "Net-(R6-PadP$1)") (class "Default")
      (node (ref "R6") (pin "P$1") (pinfunction "P$1_P$1") (pintype "bidirectional"))
      (node (ref "V6") (pin "P$1") (pinfunction "P$1_P$1") (pintype "bidirectional"))
      (node (ref "V6") (pin "P$2") (pinfunction "P$2_P$2") (pintype "bidirectional"))
    )
    (net (code "46") (name "Net-(R7-PadP$1)") (class "Default")
      (node (ref "R7") (pin "P$1") (pinfunction "P$1_P$1") (pintype "bidirectional"))
      (node (ref "V7") (pin "P$1") (pinfunction "P$1_P$1") (pintype "bidirectional"))
      (node (ref "V7") (pin "P$2") (pinfunction "P$2_P$2") (pintype "bidirectional"))
    )
    (net (code "47") (name "Net-(R8-PadP$1)") (class "Default")
      (node (ref "R8") (pin "P$1") (pinfunction "P$1_P$1") (pintype "bidirectional"))
      (node (ref "V8") (pin "P$1") (pinfunction "P$1_P$1") (pintype "bidirectional"))
      (node (ref "V8") (pin "P$2") (pinfunction "P$2_P$2") (pintype "bidirectional"))
    )
    (net (code "48") (name "Net-(R9-PadP$1)") (class "Default")
      (node (ref "R9") (pin "P$1") (pinfunction "P$1_P$1") (pintype "bidirectional"))
      (node (ref "V9") (pin "P$1") (pinfunction "P$1_P$1") (pintype "bidirectional"))
      (node (ref "V9") (pin "P$2") (pinfunction "P$2_P$2") (pintype "bidirectional"))
    )
    (net (code "49") (name "Net-(R10-PadP$1)") (class "Default")
      (node (ref "R10") (pin "P$1") (pinfunction "P$1_P$1") (pintype "bidirectional"))
      (node (ref "V10") (pin "P$1") (pinfunction "P$1_P$1") (pintype "bidirectional"))
      (node (ref "V10") (pin "P$2") (pinfunction "P$2_P$2") (pintype "bidirectional"))
    )
    (net (code "50") (name "Net-(R11-PadP$1)") (class "Default")
      (node (ref "R11") (pin "P$1") (pinfunction "P$1_P$1") (pintype "bidirectional"))
      (node (ref "V11") (pin "P$1") (pinfunction "P$1_P$1") (pintype "bidirectional"))
      (node (ref "V11") (pin "P$2") (pinfunction "P$2_P$2") (pintype "bidirectional"))
    )
    (net (code "51") (name "Net-(R12-PadP$1)") (class "Default")
      (node (ref "R12") (pin "P$1") (pinfunction "P$1_P$1") (pintype "bidirectional"))
      (node (ref "V12") (pin "P$1") (pinfunction "P$1_P$1") (pintype "bidirectional"))
      (node (ref "V12") (pin "P$2") (pinfunction "P$2_P$2") (pintype "bidirectional"))
    )
    (net (code "52") (name "Net-(R13-PadP$1)") (class "Default")
      (node (ref "R13") (pin "P$1") (pinfunction "P$1_P$1") (pintype "bidirectional"))
      (node (ref "V13") (pin "P$1") (pinfunction "P$1_P$1") (pintype "bidirectional"))
      (node (ref "V13") (pin "P$2") (pinfunction "P$2_P$2") (pintype "bidirectional"))
    )
    (net (code "53") (name "Net-(R14-PadP$1)") (class "Default")
      (node (ref "R14") (pin "P$1") (pinfunction "P$1_P$1") (pintype "bidirectional"))
      (node (ref "V14") (pin "P$1") (pinfunction "P$1_P$1") (pintype "bidirectional"))
      (node (ref "V14") (pin "P$2") (pinfunction "P$2_P$2") (pintype "bidirectional"))
    )
    (net (code "54") (name "Net-(R15-PadP$1)") (class "Default")
      (node (ref "R15") (pin "P$1") (pinfunction "P$1_P$1") (pintype "bidirectional"))
      (node (ref "V15") (pin "P$1") (pinfunction "P$1_P$1") (pintype "bidirectional"))
      (node (ref "V15") (pin "P$2") (pinfunction "P$2_P$2") (pintype "bidirectional"))
    )
    (net (code "55") (name "Net-(U$7-2)") (class "Default")
      (node (ref "U$10") (pin "P$4") (pinfunction "P$4_P$4") (pintype "bidirectional"))
      (node (ref "U$7") (pin "P$2") (pinfunction "2_P$2") (pintype "bidirectional"))
    )
    (net (code "56") (name "Net-(U$9-1)") (class "Default")
      (node (ref "U$9") (pin "P$1") (pinfunction "1_P$1") (pintype "bidirectional"))
      (node (ref "U1") (pin "20") (pinfunction "AREF_20") (pintype "input"))
    )
    (net (code "57") (name "Net-(U$79-DIN)") (class "Default")
      (node (ref "U$79") (pin "P$4") (pinfunction "DIN_P$4") (pintype "bidirectional"))
      (node (ref "U$80") (pin "P$2") (pinfunction "DOUT_P$2") (pintype "bidirectional"))
    )
    (net (code "58") (name "Net-(U$80-DIN)") (class "Default")
      (node (ref "U$80") (pin "P$4") (pinfunction "DIN_P$4") (pintype "bidirectional"))
      (node (ref "U$81") (pin "P$2") (pinfunction "DOUT_P$2") (pintype "bidirectional"))
    )
    (net (code "59") (name "Net-(U$81-DIN)") (class "Default")
      (node (ref "U$81") (pin "P$4") (pinfunction "DIN_P$4") (pintype "bidirectional"))
      (node (ref "U$82") (pin "P$2") (pinfunction "DOUT_P$2") (pintype "bidirectional"))
    )
    (net (code "60") (name "Net-(U$82-DIN)") (class "Default")
      (node (ref "U$82") (pin "P$4") (pinfunction "DIN_P$4") (pintype "bidirectional"))
      (node (ref "U$83") (pin "P$2") (pinfunction "DOUT_P$2") (pintype "bidirectional"))
    )
    (net (code "61") (name "Net-(U$83-DIN)") (class "Default")
      (node (ref "U$83") (pin "P$4") (pinfunction "DIN_P$4") (pintype "bidirectional"))
      (node (ref "U$84") (pin "P$2") (pinfunction "DOUT_P$2") (pintype "bidirectional"))
    )
    (net (code "62") (name "Net-(U$84-DIN)") (class "Default")
      (node (ref "U$84") (pin "P$4") (pinfunction "DIN_P$4") (pintype "bidirectional"))
      (node (ref "U$85") (pin "P$2") (pinfunction "DOUT_P$2") (pintype "bidirectional"))
    )
    (net (code "63") (name "Net-(U$85-DIN)") (class "Default")
      (node (ref "U$85") (pin "P$4") (pinfunction "DIN_P$4") (pintype "bidirectional"))
      (node (ref "U$86") (pin "P$2") (pinfunction "DOUT_P$2") (pintype "bidirectional"))
    )
    (net (code "64") (name "Net-(U$86-DIN)") (class "Default")
      (node (ref "U$86") (pin "P$4") (pinfunction "DIN_P$4") (pintype "bidirectional"))
      (node (ref "U$87") (pin "P$2") (pinfunction "DOUT_P$2") (pintype "bidirectional"))
    )
    (net (code "65") (name "Net-(U$87-DIN)") (class "Default")
      (node (ref "U$87") (pin "P$4") (pinfunction "DIN_P$4") (pintype "bidirectional"))
      (node (ref "U$88") (pin "P$2") (pinfunction "DOUT_P$2") (pintype "bidirectional"))
    )
    (net (code "66") (name "Net-(U$88-DIN)") (class "Default")
      (node (ref "U$88") (pin "P$4") (pinfunction "DIN_P$4") (pintype "bidirectional"))
      (node (ref "U$89") (pin "P$2") (pinfunction "DOUT_P$2") (pintype "bidirectional"))
    )
    (net (code "67") (name "Net-(U$89-DIN)") (class "Default")
      (node (ref "U$89") (pin "P$4") (pinfunction "DIN_P$4") (pintype "bidirectional"))
      (node (ref "U$90") (pin "P$2") (pinfunction "DOUT_P$2") (pintype "bidirectional"))
    )
    (net (code "68") (name "Net-(U$90-DIN)") (class "Default")
      (node (ref "U$90") (pin "P$4") (pinfunction "DIN_P$4") (pintype "bidirectional"))
      (node (ref "U$91") (pin "P$2") (pinfunction "DOUT_P$2") (pintype "bidirectional"))
    )
    (net (code "69") (name "Net-(U$91-DIN)") (class "Default")
      (node (ref "U$91") (pin "P$4") (pinfunction "DIN_P$4") (pintype "bidirectional"))
      (node (ref "U$92") (pin "P$2") (pinfunction "DOUT_P$2") (pintype "bidirectional"))
    )
    (net (code "70") (name "Net-(U$92-DIN)") (class "Default")
      (node (ref "U$92") (pin "P$4") (pinfunction "DIN_P$4") (pintype "bidirectional"))
      (node (ref "U$93") (pin "P$2") (pinfunction "DOUT_P$2") (pintype "bidirectional"))
    )
    (net (code "71") (name "Net-(U$93-DIN)") (class "Default")
      (node (ref "U$93") (pin "P$4") (pinfunction "DIN_P$4") (pintype "bidirectional"))
      (node (ref "U$94") (pin "P$2") (pinfunction "DOUT_P$2") (pintype "bidirectional"))
    )
    (net (code "72") (name "Net-(U$94-DIN)") (class "Default")
      (node (ref "U$94") (pin "P$4") (pinfunction "DIN_P$4") (pintype "bidirectional"))
      (node (ref "U$95") (pin "P$2") (pinfunction "DOUT_P$2") (pintype "bidirectional"))
    )
    (net (code "73") (name "Net-(U$95-DIN)") (class "Default")
      (node (ref "U$95") (pin "P$4") (pinfunction "DIN_P$4") (pintype "bidirectional"))
      (node (ref "U$96") (pin "P$2") (pinfunction "DOUT_P$2") (pintype "bidirectional"))
    )
    (net (code "74") (name "Net-(U$96-DIN)") (class "Default")
      (node (ref "U$96") (pin "P$4") (pinfunction "DIN_P$4") (pintype "bidirectional"))
      (node (ref "U$97") (pin "P$2") (pinfunction "DOUT_P$2") (pintype "bidirectional"))
    )
    (net (code "75") (name "Net-(U1-PB6)") (class "Default")
      (node (ref "U1") (pin "7") (pinfunction "PB6_7") (pintype "bidirectional"))
      (node (ref "Y1") (pin "1") (pinfunction "IN_1") (pintype "input"))
    )
    (net (code "76") (name "Net-(U1-PB7)") (class "Default")
      (node (ref "U1") (pin "8") (pinfunction "PB7_8") (pintype "bidirectional"))
      (node (ref "Y1") (pin "3") (pinfunction "OUT_3") (pintype "output"))
    )
    (net (code "77") (name "Net-(U1-PD0)") (class "Default")
      (node (ref "U$10") (pin "P$3") (pinfunction "P$3_P$3") (pintype "bidirectional"))
      (node (ref "U1") (pin "30") (pinfunction "PD0_30") (pintype "bidirectional"))
    )
    (net (code "78") (name "Net-(U1-PD1)") (class "Default")
      (node (ref "U$10") (pin "P$2") (pinfunction "P$2_P$2") (pintype "bidirectional"))
      (node (ref "U1") (pin "31") (pinfunction "PD1_31") (pintype "bidirectional"))
    )
    (net (code "79") (name "RES") (class "Default")
      (node (ref "S1") (pin "1") (pinfunction "1_1") (pintype "bidirectional"))
      (node (ref "S1") (pin "2") (pinfunction "2_2") (pintype "bidirectional"))
      (node (ref "U$15") (pin "P$7") (pinfunction "RES_P$7") (pintype "bidirectional"))
      (node (ref "U$6") (pin "P$1") (pinfunction "P$1_P$1") (pintype "bidirectional"))
      (node (ref "U$7") (pin "P$1") (pinfunction "1_P$1") (pintype "bidirectional"))
      (node (ref "U1") (pin "29") (pinfunction "PC6/~{RESET}_29") (pintype "bidirectional"))
    )
    (net (code "80") (name "SCK") (class "Default")
      (node (ref "U$15") (pin "P$6") (pinfunction "SCK_P$6") (pintype "bidirectional"))
      (node (ref "U1") (pin "17") (pinfunction "PB5_17") (pintype "bidirectional"))
    )
    (net (code "81") (name "SS") (class "Default")
      (node (ref "U$15") (pin "P$3") (pinfunction "SS_P$3") (pintype "bidirectional"))
      (node (ref "U1") (pin "14") (pinfunction "PB2_14") (pintype "bidirectional"))
    )
    (net (code "82") (name "unconnected-(U$79-DOUT-PadP$2)") (class "Default")
      (node (ref "U$79") (pin "P$2") (pinfunction "DOUT_P$2") (pintype "bidirectional"))
    )
    (net (code "83") (name "unconnected-(U1-ADC6-Pad19)") (class "Default")
      (node (ref "U1") (pin "19") (pinfunction "ADC6_19") (pintype "bidirectional"))
    )
    (net (code "84") (name "unconnected-(U1-ADC7-Pad22)") (class "Default")
      (node (ref "U1") (pin "22") (pinfunction "ADC7_22") (pintype "bidirectional"))
    )
  )
)
